# FireFly.net
KiCad netlist of a schematic drawn in Altium Designer
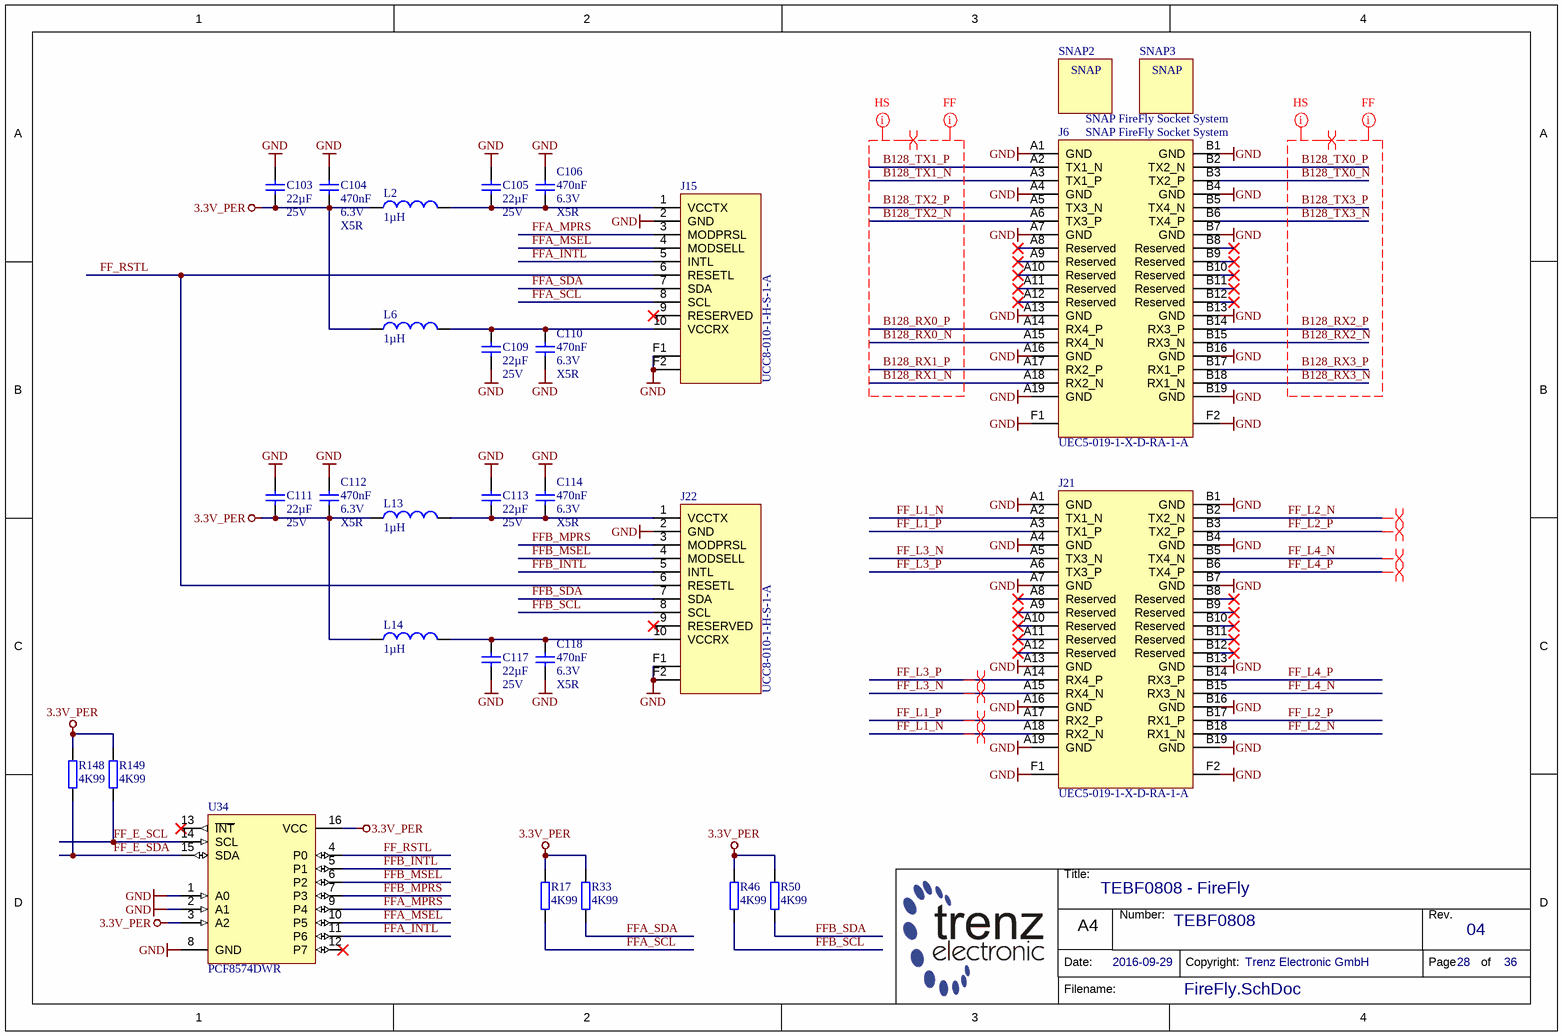
[diagram p0: FireFly.SchDoc]

(export (version "E")
  (design (tool "Eeschema 10.0.6"))
  (components
    (comp (ref "C103")
      (value "22µF")
      (footprint "CAPC3216X180N")
      (description "KON 22µF X5R 25V SMD 10%")
      (fields (field (name "VOLTAGE") "25V") (field (name "TOLERANCE") "10%"))
      (libsource (lib "TE") (part "CAP-NP"))
    )
    (comp (ref "C104")
      (value "470nF")
      (footprint "CAPC1005X55N")
      (description "KON 470nF 6,3V X5R SMD")
      (fields (field (name "VOLTAGE") "6.3V") (field (name "TECHNOLOGY") "X5R"))
      (libsource (lib "TE") (part "CAP-NP"))
    )
    (comp (ref "C105")
      (value "22µF")
      (footprint "CAPC3216X180N")
      (description "KON 22µF X5R 25V SMD 10%")
      (fields (field (name "VOLTAGE") "25V") (field (name "TOLERANCE") "10%"))
      (libsource (lib "TE") (part "CAP-NP"))
    )
    (comp (ref "C106")
      (value "470nF")
      (footprint "CAPC1005X55N")
      (description "KON 470nF 6,3V X5R SMD")
      (fields (field (name "VOLTAGE") "6.3V") (field (name "TECHNOLOGY") "X5R"))
      (libsource (lib "TE") (part "CAP-NP"))
    )
    (comp (ref "C109")
      (value "22µF")
      (footprint "CAPC3216X180N")
      (description "KON 22µF X5R 25V SMD 10%")
      (fields (field (name "VOLTAGE") "25V") (field (name "TOLERANCE") "10%"))
      (libsource (lib "TE") (part "CAP-NP"))
    )
    (comp (ref "C110")
      (value "470nF")
      (footprint "CAPC1005X55N")
      (description "KON 470nF 6,3V X5R SMD")
      (fields (field (name "VOLTAGE") "6.3V") (field (name "TECHNOLOGY") "X5R"))
      (libsource (lib "TE") (part "CAP-NP"))
    )
    (comp (ref "C111")
      (value "22µF")
      (footprint "CAPC3216X180N")
      (description "KON 22µF X5R 25V SMD 10%")
      (fields (field (name "VOLTAGE") "25V") (field (name "TOLERANCE") "10%"))
      (libsource (lib "TE") (part "CAP-NP"))
    )
    (comp (ref "C112")
      (value "470nF")
      (footprint "CAPC1005X55N")
      (description "KON 470nF 6,3V X5R SMD")
      (fields (field (name "VOLTAGE") "6.3V") (field (name "TECHNOLOGY") "X5R"))
      (libsource (lib "TE") (part "CAP-NP"))
    )
    (comp (ref "C113")
      (value "22µF")
      (footprint "CAPC3216X180N")
      (description "KON 22µF X5R 25V SMD 10%")
      (fields (field (name "VOLTAGE") "25V") (field (name "TOLERANCE") "10%"))
      (libsource (lib "TE") (part "CAP-NP"))
    )
    (comp (ref "C114")
      (value "470nF")
      (footprint "CAPC1005X55N")
      (description "KON 470nF 6,3V X5R SMD")
      (fields (field (name "VOLTAGE") "6.3V") (field (name "TECHNOLOGY") "X5R"))
      (libsource (lib "TE") (part "CAP-NP"))
    )
    (comp (ref "C117")
      (value "22µF")
      (footprint "CAPC3216X180N")
      (description "KON 22µF X5R 25V SMD 10%")
      (fields (field (name "VOLTAGE") "25V") (field (name "TOLERANCE") "10%"))
      (libsource (lib "TE") (part "CAP-NP"))
    )
    (comp (ref "C118")
      (value "470nF")
      (footprint "CAPC1005X55N")
      (description "KON 470nF 6,3V X5R SMD")
      (fields (field (name "VOLTAGE") "6.3V") (field (name "TECHNOLOGY") "X5R"))
      (libsource (lib "TE") (part "CAP-NP"))
    )
    (comp (ref "J6")
      (value "UEC5-019-1-X-D-RA-1-A")
      (footprint "UEC5-019-1-X-D-RA-1-A")
      (description "UEC5-019-1-H-D-RA-1-A")
      (libsource (lib "TE") (part "UEC5-ECUO-B04"))
    )
    (comp (ref "J15")
      (value "UCC8-010-1-H-S-1-A")
      (footprint "UCC8-010-1-X-S-1-A")
      (libsource (lib "TE") (part "UCC8"))
    )
    (comp (ref "J21")
      (value "UEC5-019-1-X-D-RA-1-A")
      (footprint "UEC5-019-1-X-D-RA-1-A")
      (description "UEC5-019-1-H-D-RA-1-A")
      (libsource (lib "TE") (part "UEC5-ECUO-B04"))
    )
    (comp (ref "J22")
      (value "UCC8-010-1-H-S-1-A")
      (footprint "UCC8-010-1-X-S-1-A")
      (libsource (lib "TE") (part "UCC8"))
    )
    (comp (ref "L2")
      (value "1µH")
      (footprint "INDC2520X100N")
      (description "IND SMD 1µH +-20% 0.055Ohm")
      (fields (field (name "VOLTAGE") "1.7A"))
      (libsource (lib "TE") (part "IND"))
    )
    (comp (ref "L6")
      (value "1µH")
      (footprint "INDC2520X100N")
      (description "IND SMD 1µH +-20% 0.055Ohm")
      (fields (field (name "VOLTAGE") "1.7A"))
      (libsource (lib "TE") (part "IND"))
    )
    (comp (ref "L13")
      (value "1µH")
      (footprint "INDC2520X100N")
      (description "IND SMD 1µH +-20% 0.055Ohm")
      (fields (field (name "VOLTAGE") "1.7A"))
      (libsource (lib "TE") (part "IND"))
    )
    (comp (ref "L14")
      (value "1µH")
      (footprint "INDC2520X100N")
      (description "IND SMD 1µH +-20% 0.055Ohm")
      (fields (field (name "VOLTAGE") "1.7A"))
      (libsource (lib "TE") (part "IND"))
    )
    (comp (ref "R17")
      (value "4K99")
      (footprint "RESC1005X40N")
      (description "WID SMD 4K99 1% 0,063W")
      (fields (field (name "TOLERANCE") "1%"))
      (libsource (lib "TE") (part "RES"))
    )
    (comp (ref "R33")
      (value "4K99")
      (footprint "RESC1005X40N")
      (description "WID SMD 4K99 1% 0,063W")
      (fields (field (name "TOLERANCE") "1%"))
      (libsource (lib "TE") (part "RES"))
    )
    (comp (ref "R46")
      (value "4K99")
      (footprint "RESC1005X40N")
      (description "WID SMD 4K99 1% 0,063W")
      (fields (field (name "TOLERANCE") "1%"))
      (libsource (lib "TE") (part "RES"))
    )
    (comp (ref "R50")
      (value "4K99")
      (footprint "RESC1005X40N")
      (description "WID SMD 4K99 1% 0,063W")
      (fields (field (name "TOLERANCE") "1%"))
      (libsource (lib "TE") (part "RES"))
    )
    (comp (ref "R148")
      (value "4K99")
      (footprint "RESC1005X40N")
      (description "WID SMD 4K99 1% 0,063W")
      (fields (field (name "TOLERANCE") "1%"))
      (libsource (lib "TE") (part "RES"))
    )
    (comp (ref "R149")
      (value "4K99")
      (footprint "RESC1005X40N")
      (description "WID SMD 4K99 1% 0,063W")
      (fields (field (name "TOLERANCE") "1%"))
      (libsource (lib "TE") (part "RES"))
    )
    (comp (ref "SNAP2")
      (value "SNAP FireFly Socket System")
      (footprint "FireFly_Snap")
      (libsource (lib "TE") (part "TE_76x52mm_3N_Snap"))
    )
    (comp (ref "SNAP3")
      (value "SNAP FireFly Socket System")
      (footprint "FireFly_Snap")
      (libsource (lib "TE") (part "TE_76x52mm_3N_Snap"))
    )
    (comp (ref "U34")
      (value "PCF8574DWR")
      (footprint "SOIC127P1030X265-16N")
      (libsource (lib "TE") (part "PCF8574DWR"))
    )
  )
  (nets
    (net (code "1") (name "/B128_RX0_N") (class "Default")
      (node (ref "J6") (pin "A15") (pinfunction "RX4_N_A15") (pintype "passive"))
    )
    (net (code "2") (name "/B128_RX0_P") (class "Default")
      (node (ref "J6") (pin "A14") (pinfunction "RX4_P_A14") (pintype "passive"))
    )
    (net (code "3") (name "/B128_RX1_N") (class "Default")
      (node (ref "J6") (pin "A18") (pinfunction "RX2_N_A18") (pintype "passive"))
    )
    (net (code "4") (name "/B128_RX1_P") (class "Default")
      (node (ref "J6") (pin "A17") (pinfunction "RX2_P_A17") (pintype "passive"))
    )
    (net (code "5") (name "/B128_RX2_N") (class "Default")
      (node (ref "J6") (pin "B15") (pinfunction "RX3_N_B15") (pintype "passive"))
    )
    (net (code "6") (name "/B128_RX2_P") (class "Default")
      (node (ref "J6") (pin "B14") (pinfunction "RX3_P_B14") (pintype "passive"))
    )
    (net (code "7") (name "/B128_RX3_N") (class "Default")
      (node (ref "J6") (pin "B18") (pinfunction "RX1_N_B18") (pintype "passive"))
    )
    (net (code "8") (name "/B128_RX3_P") (class "Default")
      (node (ref "J6") (pin "B17") (pinfunction "RX1_P_B17") (pintype "passive"))
    )
    (net (code "9") (name "/B128_TX0_N") (class "Default")
      (node (ref "J6") (pin "B3") (pinfunction "TX2_P_B3") (pintype "passive"))
    )
    (net (code "10") (name "/B128_TX0_P") (class "Default")
      (node (ref "J6") (pin "B2") (pinfunction "TX2_N_B2") (pintype "passive"))
    )
    (net (code "11") (name "/B128_TX1_N") (class "Default")
      (node (ref "J6") (pin "A3") (pinfunction "TX1_P_A3") (pintype "passive"))
    )
    (net (code "12") (name "/B128_TX1_P") (class "Default")
      (node (ref "J6") (pin "A2") (pinfunction "TX1_N_A2") (pintype "passive"))
    )
    (net (code "13") (name "/B128_TX2_N") (class "Default")
      (node (ref "J6") (pin "A6") (pinfunction "TX3_P_A6") (pintype "passive"))
    )
    (net (code "14") (name "/B128_TX2_P") (class "Default")
      (node (ref "J6") (pin "A5") (pinfunction "TX3_N_A5") (pintype "passive"))
    )
    (net (code "15") (name "/B128_TX3_N") (class "Default")
      (node (ref "J6") (pin "B6") (pinfunction "TX4_P_B6") (pintype "passive"))
    )
    (net (code "16") (name "/B128_TX3_P") (class "Default")
      (node (ref "J6") (pin "B5") (pinfunction "TX4_N_B5") (pintype "passive"))
    )
    (net (code "17") (name "/FFA_INTL") (class "Default")
      (node (ref "J15") (pin "5") (pinfunction "INTL_5") (pintype "passive"))
      (node (ref "U34") (pin "11") (pinfunction "P6_11") (pintype "bidirectional"))
    )
    (net (code "18") (name "/FFA_MPRS") (class "Default")
      (node (ref "J15") (pin "3") (pinfunction "MODPRSL_3") (pintype "passive"))
      (node (ref "U34") (pin "9") (pinfunction "P4_9") (pintype "bidirectional"))
    )
    (net (code "19") (name "/FFA_MSEL") (class "Default")
      (node (ref "J15") (pin "4") (pinfunction "MODSELL_4") (pintype "passive"))
      (node (ref "U34") (pin "10") (pinfunction "P5_10") (pintype "bidirectional"))
    )
    (net (code "20") (name "/FFA_SCL") (class "Default")
      (node (ref "J15") (pin "8") (pinfunction "SCL_8") (pintype "passive"))
      (node (ref "R17") (pin "2") (pinfunction "2_2") (pintype "passive"))
    )
    (net (code "21") (name "/FFA_SDA") (class "Default")
      (node (ref "J15") (pin "7") (pinfunction "SDA_7") (pintype "passive"))
      (node (ref "R33") (pin "2") (pinfunction "2_2") (pintype "passive"))
    )
    (net (code "22") (name "/FFB_INTL") (class "Default")
      (node (ref "J22") (pin "5") (pinfunction "INTL_5") (pintype "passive"))
      (node (ref "U34") (pin "5") (pinfunction "P1_5") (pintype "bidirectional"))
    )
    (net (code "23") (name "/FFB_MPRS") (class "Default")
      (node (ref "J22") (pin "3") (pinfunction "MODPRSL_3") (pintype "passive"))
      (node (ref "U34") (pin "7") (pinfunction "P3_7") (pintype "bidirectional"))
    )
    (net (code "24") (name "/FFB_MSEL") (class "Default")
      (node (ref "J22") (pin "4") (pinfunction "MODSELL_4") (pintype "passive"))
      (node (ref "U34") (pin "6") (pinfunction "P2_6") (pintype "bidirectional"))
    )
    (net (code "25") (name "/FFB_SCL") (class "Default")
      (node (ref "J22") (pin "8") (pinfunction "SCL_8") (pintype "passive"))
      (node (ref "R46") (pin "2") (pinfunction "2_2") (pintype "passive"))
    )
    (net (code "26") (name "/FFB_SDA") (class "Default")
      (node (ref "J22") (pin "7") (pinfunction "SDA_7") (pintype "passive"))
      (node (ref "R50") (pin "2") (pinfunction "2_2") (pintype "passive"))
    )
    (net (code "27") (name "/FF_E_SCL") (class "Default")
      (node (ref "R149") (pin "2") (pinfunction "2_2") (pintype "passive"))
      (node (ref "U34") (pin "14") (pinfunction "SCL_14") (pintype "input"))
    )
    (net (code "28") (name "/FF_E_SDA") (class "Default")
      (node (ref "R148") (pin "2") (pinfunction "2_2") (pintype "passive"))
      (node (ref "U34") (pin "15") (pinfunction "SDA_15") (pintype "bidirectional"))
    )
    (net (code "29") (name "/FF_L1_N") (class "Default")
      (node (ref "J21") (pin "A18") (pinfunction "RX2_N_A18") (pintype "passive"))
      (node (ref "J21") (pin "A2") (pinfunction "TX1_N_A2") (pintype "passive"))
    )
    (net (code "30") (name "/FF_L1_P") (class "Default")
      (node (ref "J21") (pin "A17") (pinfunction "RX2_P_A17") (pintype "passive"))
      (node (ref "J21") (pin "A3") (pinfunction "TX1_P_A3") (pintype "passive"))
    )
    (net (code "31") (name "/FF_L2_N") (class "Default")
      (node (ref "J21") (pin "B18") (pinfunction "RX1_N_B18") (pintype "passive"))
      (node (ref "J21") (pin "B2") (pinfunction "TX2_N_B2") (pintype "passive"))
    )
    (net (code "32") (name "/FF_L2_P") (class "Default")
      (node (ref "J21") (pin "B17") (pinfunction "RX1_P_B17") (pintype "passive"))
      (node (ref "J21") (pin "B3") (pinfunction "TX2_P_B3") (pintype "passive"))
    )
    (net (code "33") (name "/FF_L3_N") (class "Default")
      (node (ref "J21") (pin "A15") (pinfunction "RX4_N_A15") (pintype "passive"))
      (node (ref "J21") (pin "A5") (pinfunction "TX3_N_A5") (pintype "passive"))
    )
    (net (code "34") (name "/FF_L3_P") (class "Default")
      (node (ref "J21") (pin "A14") (pinfunction "RX4_P_A14") (pintype "passive"))
      (node (ref "J21") (pin "A6") (pinfunction "TX3_P_A6") (pintype "passive"))
    )
    (net (code "35") (name "/FF_L4_N") (class "Default")
      (node (ref "J21") (pin "B15") (pinfunction "RX3_N_B15") (pintype "passive"))
      (node (ref "J21") (pin "B5") (pinfunction "TX4_N_B5") (pintype "passive"))
    )
    (net (code "36") (name "/FF_L4_P") (class "Default")
      (node (ref "J21") (pin "B14") (pinfunction "RX3_P_B14") (pintype "passive"))
      (node (ref "J21") (pin "B6") (pinfunction "TX4_P_B6") (pintype "passive"))
    )
    (net (code "37") (name "/FF_RSTL") (class "Default")
      (node (ref "J15") (pin "6") (pinfunction "RESETL_6") (pintype "passive"))
      (node (ref "J22") (pin "6") (pinfunction "RESETL_6") (pintype "passive"))
      (node (ref "U34") (pin "4") (pinfunction "P0_4") (pintype "bidirectional"))
    )
    (net (code "38") (name "3.3V_PER") (class "Default")
      (node (ref "C103") (pin "2") (pinfunction "2_2") (pintype "passive"))
      (node (ref "C104") (pin "2") (pinfunction "2_2") (pintype "passive"))
      (node (ref "C111") (pin "2") (pinfunction "2_2") (pintype "passive"))
      (node (ref "C112") (pin "2") (pinfunction "2_2") (pintype "passive"))
      (node (ref "L13") (pin "1") (pinfunction "1_1") (pintype "passive"))
      (node (ref "L14") (pin "1") (pinfunction "1_1") (pintype "passive"))
      (node (ref "L2") (pin "1") (pinfunction "1_1") (pintype "passive"))
      (node (ref "L6") (pin "1") (pinfunction "1_1") (pintype "passive"))
      (node (ref "R148") (pin "1") (pinfunction "1_1") (pintype "passive"))
      (node (ref "R149") (pin "1") (pinfunction "1_1") (pintype "passive"))
      (node (ref "R17") (pin "1") (pinfunction "1_1") (pintype "passive"))
      (node (ref "R33") (pin "1") (pinfunction "1_1") (pintype "passive"))
      (node (ref "R46") (pin "1") (pinfunction "1_1") (pintype "passive"))
      (node (ref "R50") (pin "1") (pinfunction "1_1") (pintype "passive"))
      (node (ref "U34") (pin "16") (pinfunction "VCC_16") (pintype "power_in"))
      (node (ref "U34") (pin "3") (pinfunction "A2_3") (pintype "input"))
    )
    (net (code "39") (name "GND") (class "Default")
      (node (ref "C103") (pin "1") (pinfunction "1_1") (pintype "passive"))
      (node (ref "C104") (pin "1") (pinfunction "1_1") (pintype "passive"))
      (node (ref "C105") (pin "2") (pinfunction "2_2") (pintype "passive"))
      (node (ref "C106") (pin "1") (pinfunction "1_1") (pintype "passive"))
      (node (ref "C109") (pin "1") (pinfunction "1_1") (pintype "passive"))
      (node (ref "C110") (pin "2") (pinfunction "2_2") (pintype "passive"))
      (node (ref "C111") (pin "1") (pinfunction "1_1") (pintype "passive"))
      (node (ref "C112") (pin "1") (pinfunction "1_1") (pintype "passive"))
      (node (ref "C113") (pin "2") (pinfunction "2_2") (pintype "passive"))
      (node (ref "C114") (pin "1") (pinfunction "1_1") (pintype "passive"))
      (node (ref "C117") (pin "1") (pinfunction "1_1") (pintype "passive"))
      (node (ref "C118") (pin "2") (pinfunction "2_2") (pintype "passive"))
      (node (ref "J15") (pin "2") (pinfunction "GND_2") (pintype "passive"))
      (node (ref "J15") (pin "F1") (pinfunction "GND_F1") (pintype "passive"))
      (node (ref "J15") (pin "F2") (pinfunction "GND_F2") (pintype "passive"))
      (node (ref "J21") (pin "A1") (pinfunction "GND_A1") (pintype "passive"))
      (node (ref "J21") (pin "A13") (pinfunction "GND_A13") (pintype "passive"))
      (node (ref "J21") (pin "A16") (pinfunction "GND_A16") (pintype "passive"))
      (node (ref "J21") (pin "A19") (pinfunction "GND_A19") (pintype "passive"))
      (node (ref "J21") (pin "A4") (pinfunction "GND_A4") (pintype "passive"))
      (node (ref "J21") (pin "A7") (pinfunction "GND_A7") (pintype "passive"))
      (node (ref "J21") (pin "B1") (pinfunction "GND_B1") (pintype "passive"))
      (node (ref "J21") (pin "B13") (pinfunction "GND_B13") (pintype "passive"))
      (node (ref "J21") (pin "B16") (pinfunction "GND_B16") (pintype "passive"))
      (node (ref "J21") (pin "B19") (pinfunction "GND_B19") (pintype "passive"))
      (node (ref "J21") (pin "B4") (pinfunction "GND_B4") (pintype "passive"))
      (node (ref "J21") (pin "B7") (pinfunction "GND_B7") (pintype "passive"))
      (node (ref "J21") (pin "F1") (pinfunction "GND_F1") (pintype "passive"))
      (node (ref "J21") (pin "F2") (pinfunction "GND_F2") (pintype "passive"))
      (node (ref "J22") (pin "2") (pinfunction "GND_2") (pintype "passive"))
      (node (ref "J22") (pin "F1") (pinfunction "GND_F1") (pintype "passive"))
      (node (ref "J22") (pin "F2") (pinfunction "GND_F2") (pintype "passive"))
      (node (ref "J6") (pin "A1") (pinfunction "GND_A1") (pintype "passive"))
      (node (ref "J6") (pin "A13") (pinfunction "GND_A13") (pintype "passive"))
      (node (ref "J6") (pin "A16") (pinfunction "GND_A16") (pintype "passive"))
      (node (ref "J6") (pin "A19") (pinfunction "GND_A19") (pintype "passive"))
      (node (ref "J6") (pin "A4") (pinfunction "GND_A4") (pintype "passive"))
      (node (ref "J6") (pin "A7") (pinfunction "GND_A7") (pintype "passive"))
      (node (ref "J6") (pin "B1") (pinfunction "GND_B1") (pintype "passive"))
      (node (ref "J6") (pin "B13") (pinfunction "GND_B13") (pintype "passive"))
      (node (ref "J6") (pin "B16") (pinfunction "GND_B16") (pintype "passive"))
      (node (ref "J6") (pin "B19") (pinfunction "GND_B19") (pintype "passive"))
      (node (ref "J6") (pin "B4") (pinfunction "GND_B4") (pintype "passive"))
      (node (ref "J6") (pin "B7") (pinfunction "GND_B7") (pintype "passive"))
      (node (ref "J6") (pin "F1") (pinfunction "GND_F1") (pintype "passive"))
      (node (ref "J6") (pin "F2") (pinfunction "GND_F2") (pintype "passive"))
      (node (ref "U34") (pin "1") (pinfunction "A0_1") (pintype "input"))
      (node (ref "U34") (pin "2") (pinfunction "A1_2") (pintype "input"))
      (node (ref "U34") (pin "8") (pinfunction "GND_8") (pintype "power_in"))
    )
    (net (code "40") (name "Net-(J15-VCCRX)") (class "Default")
      (node (ref "C109") (pin "2") (pinfunction "2_2") (pintype "passive"))
      (node (ref "C110") (pin "1") (pinfunction "1_1") (pintype "passive"))
      (node (ref "J15") (pin "10") (pinfunction "VCCRX_10") (pintype "passive"))
      (node (ref "L6") (pin "2") (pinfunction "2_2") (pintype "passive"))
    )
    (net (code "41") (name "Net-(J15-VCCTX)") (class "Default")
      (node (ref "C105") (pin "1") (pinfunction "1_1") (pintype "passive"))
      (node (ref "C106") (pin "2") (pinfunction "2_2") (pintype "passive"))
      (node (ref "J15") (pin "1") (pinfunction "VCCTX_1") (pintype "passive"))
      (node (ref "L2") (pin "2") (pinfunction "2_2") (pintype "passive"))
    )
    (net (code "42") (name "Net-(J22-VCCRX)") (class "Default")
      (node (ref "C117") (pin "2") (pinfunction "2_2") (pintype "passive"))
      (node (ref "C118") (pin "1") (pinfunction "1_1") (pintype "passive"))
      (node (ref "J22") (pin "10") (pinfunction "VCCRX_10") (pintype "passive"))
      (node (ref "L14") (pin "2") (pinfunction "2_2") (pintype "passive"))
    )
    (net (code "43") (name "Net-(J22-VCCTX)") (class "Default")
      (node (ref "C113") (pin "1") (pinfunction "1_1") (pintype "passive"))
      (node (ref "C114") (pin "2") (pinfunction "2_2") (pintype "passive"))
      (node (ref "J22") (pin "1") (pinfunction "VCCTX_1") (pintype "passive"))
      (node (ref "L13") (pin "2") (pinfunction "2_2") (pintype "passive"))
    )
    (net (code "44") (name "unconnected-(J6-Reserved-PadA8)") (class "Default")
      (node (ref "J6") (pin "A8") (pinfunction "Reserved_A8") (pintype "passive+no_connect"))
    )
    (net (code "45") (name "unconnected-(J6-Reserved-PadA9)") (class "Default")
      (node (ref "J6") (pin "A9") (pinfunction "Reserved_A9") (pintype "passive+no_connect"))
    )
    (net (code "46") (name "unconnected-(J6-Reserved-PadA10)") (class "Default")
      (node (ref "J6") (pin "A10") (pinfunction "Reserved_A10") (pintype "passive+no_connect"))
    )
    (net (code "47") (name "unconnected-(J6-Reserved-PadA11)") (class "Default")
      (node (ref "J6") (pin "A11") (pinfunction "Reserved_A11") (pintype "passive+no_connect"))
    )
    (net (code "48") (name "unconnected-(J6-Reserved-PadA12)") (class "Default")
      (node (ref "J6") (pin "A12") (pinfunction "Reserved_A12") (pintype "passive+no_connect"))
    )
    (net (code "49") (name "unconnected-(J6-Reserved-PadB8)") (class "Default")
      (node (ref "J6") (pin "B8") (pinfunction "Reserved_B8") (pintype "passive+no_connect"))
    )
    (net (code "50") (name "unconnected-(J6-Reserved-PadB9)") (class "Default")
      (node (ref "J6") (pin "B9") (pinfunction "Reserved_B9") (pintype "passive+no_connect"))
    )
    (net (code "51") (name "unconnected-(J6-Reserved-PadB10)") (class "Default")
      (node (ref "J6") (pin "B10") (pinfunction "Reserved_B10") (pintype "passive+no_connect"))
    )
    (net (code "52") (name "unconnected-(J6-Reserved-PadB11)") (class "Default")
      (node (ref "J6") (pin "B11") (pinfunction "Reserved_B11") (pintype "passive+no_connect"))
    )
    (net (code "53") (name "unconnected-(J6-Reserved-PadB12)") (class "Default")
      (node (ref "J6") (pin "B12") (pinfunction "Reserved_B12") (pintype "passive+no_connect"))
    )
    (net (code "54") (name "unconnected-(J15-RESERVED-Pad9)") (class "Default")
      (node (ref "J15") (pin "9") (pinfunction "RESERVED_9") (pintype "passive+no_connect"))
    )
    (net (code "55") (name "unconnected-(J21-Reserved-PadA8)") (class "Default")
      (node (ref "J21") (pin "A8") (pinfunction "Reserved_A8") (pintype "passive+no_connect"))
    )
    (net (code "56") (name "unconnected-(J21-Reserved-PadA9)") (class "Default")
      (node (ref "J21") (pin "A9") (pinfunction "Reserved_A9") (pintype "passive+no_connect"))
    )
    (net (code "57") (name "unconnected-(J21-Reserved-PadA10)") (class "Default")
      (node (ref "J21") (pin "A10") (pinfunction "Reserved_A10") (pintype "passive+no_connect"))
    )
    (net (code "58") (name "unconnected-(J21-Reserved-PadA11)") (class "Default")
      (node (ref "J21") (pin "A11") (pinfunction "Reserved_A11") (pintype "passive+no_connect"))
    )
    (net (code "59") (name "unconnected-(J21-Reserved-PadA12)") (class "Default")
      (node (ref "J21") (pin "A12") (pinfunction "Reserved_A12") (pintype "passive+no_connect"))
    )
    (net (code "60") (name "unconnected-(J21-Reserved-PadB8)") (class "Default")
      (node (ref "J21") (pin "B8") (pinfunction "Reserved_B8") (pintype "passive+no_connect"))
    )
    (net (code "61") (name "unconnected-(J21-Reserved-PadB9)") (class "Default")
      (node (ref "J21") (pin "B9") (pinfunction "Reserved_B9") (pintype "passive+no_connect"))
    )
    (net (code "62") (name "unconnected-(J21-Reserved-PadB10)") (class "Default")
      (node (ref "J21") (pin "B10") (pinfunction "Reserved_B10") (pintype "passive+no_connect"))
    )
    (net (code "63") (name "unconnected-(J21-Reserved-PadB11)") (class "Default")
      (node (ref "J21") (pin "B11") (pinfunction "Reserved_B11") (pintype "passive+no_connect"))
    )
    (net (code "64") (name "unconnected-(J21-Reserved-PadB12)") (class "Default")
      (node (ref "J21") (pin "B12") (pinfunction "Reserved_B12") (pintype "passive+no_connect"))
    )
    (net (code "65") (name "unconnected-(J22-RESERVED-Pad9)") (class "Default")
      (node (ref "J22") (pin "9") (pinfunction "RESERVED_9") (pintype "passive+no_connect"))
    )
    (net (code "66") (name "unconnected-(U34-P7-Pad12)") (class "Default")
      (node (ref "U34") (pin "12") (pinfunction "P7_12") (pintype "bidirectional+no_connect"))
    )
    (net (code "67") (name "unconnected-(U34-~{INT}-Pad13)") (class "Default")
      (node (ref "U34") (pin "13") (pinfunction "~{INT}_13") (pintype "output+no_connect"))
    )
  )
)
